# Power.net
KiCad netlist of a schematic drawn in Altium Designer
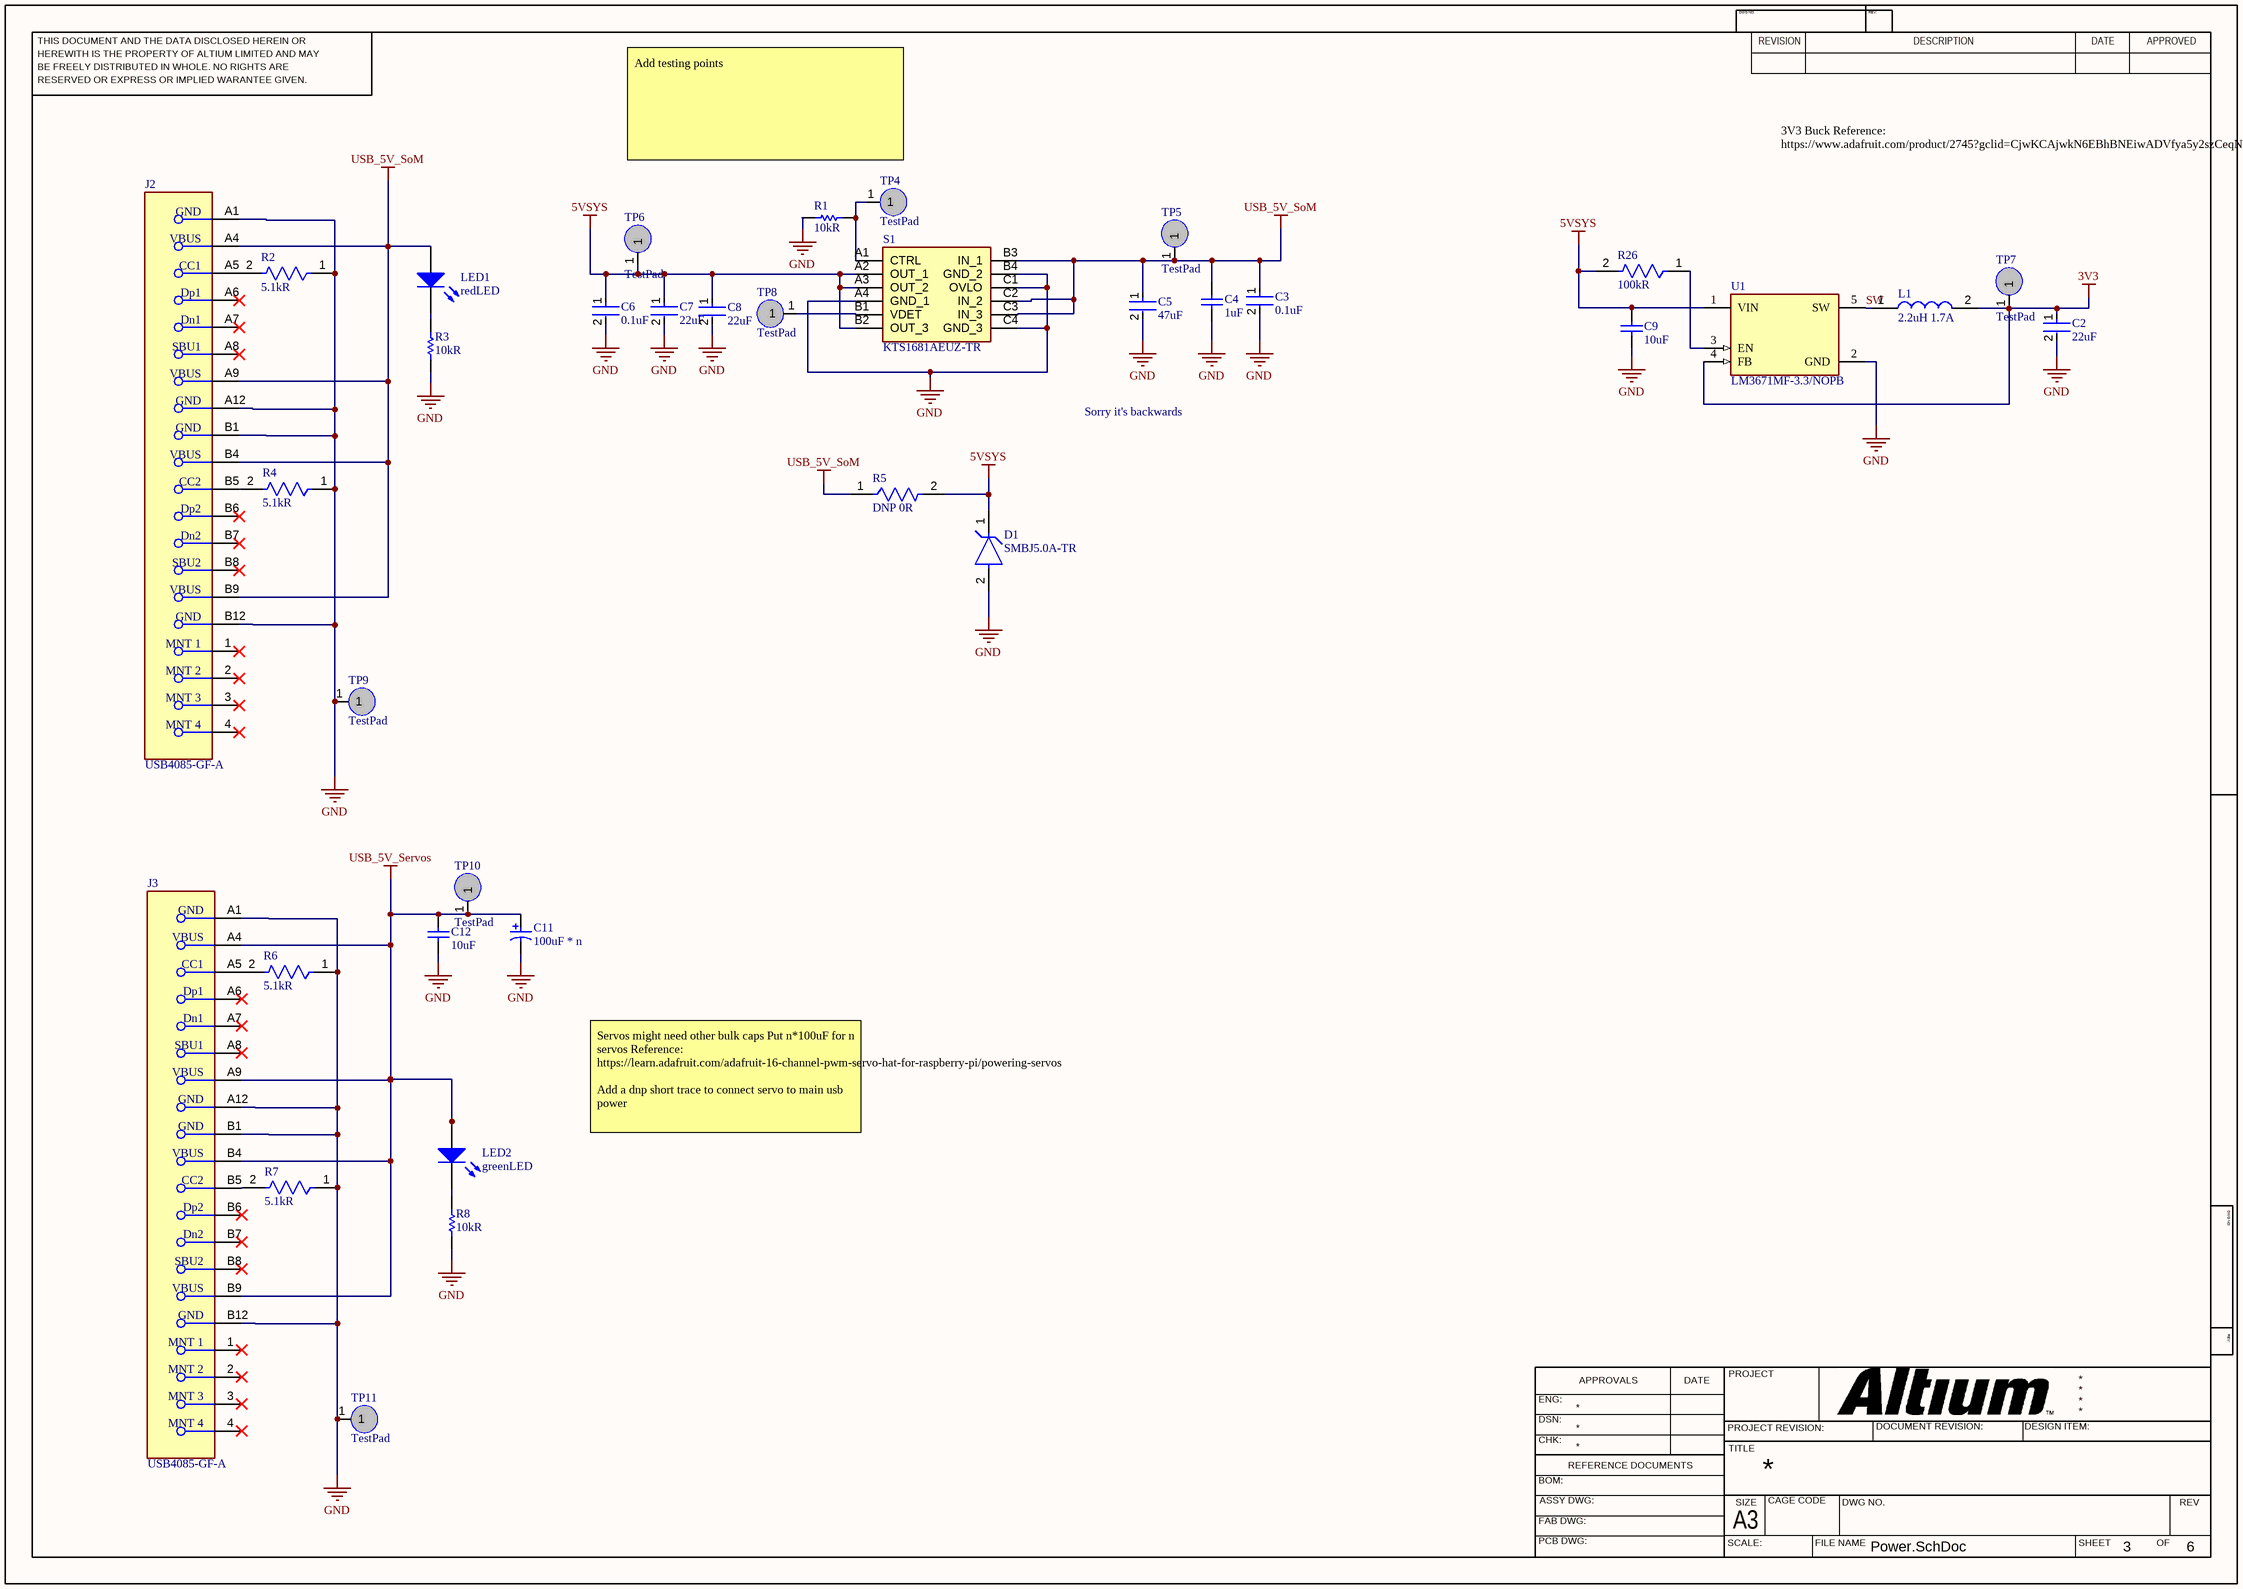
[diagram p0: Power.SchDoc]

(export (version "E")
  (design (tool "Eeschema 10.0.6"))
  (components
    (comp (ref "C2")
      (value "22uF")
      (footprint "FP-GRM21B-0_15-MFG")
      (fields (field (name "VOLTAGE") "6.3V") (field (name "TOLERANCE") "20%"))
      (libsource (lib "Altium Content Vault") (part "b4654b650e69147ec39a6b967a45e02"))
    )
    (comp (ref "C3")
      (value "0.1uF")
      (footprint "FP-C0603-CJ-MFG")
      (description "C0603X104K5RACTU CAP CER 0.1UF 50V X7R 0603")
      (fields (field (name "MANUFACTURER PART NUMBER") "C0603X104K5RACTU") (field (name "VOLTAGE") "50V"))
      (libsource (lib "Altium Content Vault") (part "11868f565c42a9108669ba33697ecf6"))
    )
    (comp (ref "C4")
      (value "1uF")
      (footprint "CAPC2013X145X50LL20T25")
      (description "C0805C105K4PACTU")
      (fields (field (name "MANUFACTURER") "Kemet"))
      (libsource (lib "Altium Content Vault") (part "CAP"))
    )
    (comp (ref "C5")
      (value "47uF")
      (footprint "FP-GRM31C-0_2-e0_3_0_8-IPC_C")
      (fields (field (name "TOLERANCE") "20%") (field (name "VOLTAGE") "6.3V"))
      (libsource (lib "Altium Content Vault") (part "02cd4be3c70576c341d710602a673aa"))
    )
    (comp (ref "C6")
      (value "0.1uF")
      (footprint "FP-C0603-CJ-MFG")
      (description "C0603X104K5RACTU CAP CER 0.1UF 50V X7R 0603")
      (fields (field (name "MANUFACTURER PART NUMBER") "C0603X104K5RACTU") (field (name "VOLTAGE") "50V"))
      (libsource (lib "Altium Content Vault") (part "11868f565c42a9108669ba33697ecf6"))
    )
    (comp (ref "C7")
      (value "22uF")
      (footprint "FP-GRM21B-0_15-MFG")
      (fields (field (name "VOLTAGE") "6.3V") (field (name "TOLERANCE") "20%"))
      (libsource (lib "Altium Content Vault") (part "b4654b650e69147ec39a6b967a45e02"))
    )
    (comp (ref "C8")
      (value "22uF")
      (footprint "FP-GRM21B-0_15-MFG")
      (fields (field (name "VOLTAGE") "6.3V") (field (name "TOLERANCE") "20%"))
      (libsource (lib "Altium Content Vault") (part "b4654b650e69147ec39a6b967a45e02"))
    )
    (comp (ref "C9")
      (value "10uF")
      (footprint "CAPC2013X145X20ML20")
      (fields
        (field (name "MANUFACTURER") "TDK")
        (field (name "TOLERANCE") "±10%")
        (field (name "PCN PART NUMBER") "MLCCPartNumberChange30/Nov/2012")
      )
      (libsource (lib "Altium Content Vault") (part "CAP-NP-2"))
    )
    (comp (ref "C11")
      (value "100uF * n")
      (footprint "CAPPR65-500-2000X1250X2200")
      (fields (field (name "MANUFACTURER") "Panasonic"))
      (libsource (lib "Altium Content Vault") (part "CAP-P-2"))
    )
    (comp (ref "C12")
      (value "10uF")
      (footprint "CAPC2013X145X20ML20")
      (fields
        (field (name "MANUFACTURER") "TDK")
        (field (name "TOLERANCE") "±10%")
        (field (name "PCN PART NUMBER") "MLCCPartNumberChange30/Nov/2012")
      )
      (libsource (lib "Altium Content Vault") (part "CAP-NP-2"))
    )
    (comp (ref "D1")
      (value "SMBJ5.0A-TR")
      (footprint "FP-SMB-MFG")
      (description "TVS DIODE 5V 13.4V SMB")
      (fields
        (field (name "MANUFACTURER") "STMicroelectronics")
        (field (name "OCTOPART") "https://octopart.com/smbj5.0a-tr-stmicroelectronics-347079")
      )
      (libsource (lib "Altium Content Vault") (part "7ddec9f632b8482e96f7745d0fbdf39"))
    )
    (comp (ref "J2")
      (value "USB4085-GF-A")
      (footprint "FP-USB4085-GF-A-MFG")
      (description "CONN RCPT USB2.0 TYPEC 16POS")
      (fields
        (field (name "MANUFACTURER") "Global Connector Technology")
        (field (name "OCTOPART") "https://octopart.com/usb4085-gf-a-global+connector+technology-94773699")
      )
      (libsource (lib "Altium Content Vault") (part "f6997dba88850a18107ac0013977506"))
    )
    (comp (ref "J3")
      (value "USB4085-GF-A")
      (footprint "FP-USB4085-GF-A-MFG")
      (description "CONN RCPT USB2.0 TYPEC 16POS")
      (fields
        (field (name "MANUFACTURER") "Global Connector Technology")
        (field (name "OCTOPART") "https://octopart.com/usb4085-gf-a-global+connector+technology-94773699")
      )
      (libsource (lib "Altium Content Vault") (part "f6997dba88850a18107ac0013977506"))
    )
    (comp (ref "L1")
      (value "2.2uH 1.7A")
      (footprint "LayoutFootprintsGoogle:NRH2412T2R2MNGH")
      (description "Inductor NRH2412T2R2MNGH")
      (fields
        (field (name "MANUFACTURER_PART_NUMBER") "NRH2412T2R2MNGH")
        (field (name "MOUSER PART NUMBER") "963-NRH2412T2R2MNGH")
      )
      (libsource (lib "*") (part "NRH2412T2R2MNGH"))
    )
    (comp (ref "LED1")
      (value "redLED")
      (footprint "0805_A")
      (description "SMD mono-color Chip LED, WL-SMCW, Super Red")
      (fields (field (name "MANUFACTURER") "Wuerth Elektronik") (field (name "PARTNUMBER") "150080SS75000"))
      (libsource (lib "Altium Content Vault") (part "WE-LED_K1A2-2"))
    )
    (comp (ref "LED2")
      (value "greenLED")
      (footprint "0805_A")
      (description "SMD mono-color Chip LED, WL-SMCW, Green")
      (fields (field (name "PARTNUMBER") "150080GS75000") (field (name "MANUFACTURER") "Wuerth Elektronik"))
      (libsource (lib "Altium Content Vault") (part "WE-LED_K1A2-2"))
    )
    (comp (ref "R1")
      (value "10kR")
      (footprint "RESC2013X60X35NL10T20")
      (fields (field (name "MANUFACTURER") "Yageo"))
      (libsource (lib "Altium Content Vault") (part "RES-2"))
    )
    (comp (ref "R2")
      (value "5.1kR")
      (footprint "FP-CRCW0805-e3-MFG")
      (description "RES Thick Film, 5.1kΩ, 1%, 0.125W, 100ppm/°C, 0805 CRCW08055K10FKEA")
      (fields (field (name "TOLERANCE") "1%"))
      (libsource (lib "Altium Content Vault") (part "1029c3af85768c4190bb7ad29bc67b5"))
    )
    (comp (ref "R3")
      (value "10kR")
      (footprint "RESC2013X60X35ML10T20")
      (fields (field (name "TOLERANCE") "1%") (field (name "MANUFACTURER") "Yageo"))
      (libsource (lib "Altium Content Vault") (part "RES-2"))
    )
    (comp (ref "R4")
      (value "5.1kR")
      (footprint "FP-CRCW0805-e3-MFG")
      (description "RES Thick Film, 5.1kΩ, 1%, 0.125W, 100ppm/°C, 0805 CRCW08055K10FKEA")
      (fields (field (name "TOLERANCE") "1%"))
      (libsource (lib "Altium Content Vault") (part "1029c3af85768c4190bb7ad29bc67b5"))
    )
    (comp (ref "R5")
      (value "DNP 0R")
      (footprint "FP-RC1206-MFG")
      (description "RC1206JR-070RL RES SMD 0 OHM JUMPER 1/4W 1206")
      (fields
        (field (name "MANUFACTURER PART NUMBER") "RC1206JR-070RL")
        (field (name "MANUFACTURER") "YAGEO")
      )
      (libsource (lib "Altium Content Vault") (part "1029c3af85768c4190bb7ad29bc67b5"))
    )
    (comp (ref "R6")
      (value "5.1kR")
      (footprint "FP-CRCW0805-e3-MFG")
      (description "RES Thick Film, 5.1kΩ, 1%, 0.125W, 100ppm/°C, 0805 CRCW08055K10FKEA")
      (fields (field (name "TOLERANCE") "1%"))
      (libsource (lib "Altium Content Vault") (part "1029c3af85768c4190bb7ad29bc67b5"))
    )
    (comp (ref "R7")
      (value "5.1kR")
      (footprint "FP-CRCW0805-e3-MFG")
      (description "RES Thick Film, 5.1kΩ, 1%, 0.125W, 100ppm/°C, 0805 CRCW08055K10FKEA")
      (fields (field (name "TOLERANCE") "1%"))
      (libsource (lib "Altium Content Vault") (part "1029c3af85768c4190bb7ad29bc67b5"))
    )
    (comp (ref "R8")
      (value "10kR")
      (footprint "RESC2013X60X35ML10T20")
      (fields (field (name "TOLERANCE") "1%") (field (name "MANUFACTURER") "Yageo"))
      (libsource (lib "Altium Content Vault") (part "RES-2"))
    )
    (comp (ref "R26")
      (value "100kR")
      (footprint "FP-RC0603-0_55-MFG")
      (description "RC0603FR-07100KL RES SMD 100K OHM 1% 1/10W 0603")
      (fields (field (name "TOLERANCE") "1%"))
      (libsource (lib "Altium Content Vault") (part "1029c3af85768c4190bb7ad29bc67b5"))
    )
    (comp (ref "S1")
      (value "KTS1681AEUZ-TR")
      (footprint "LayoutFootprintsGoogle:KTS1681AEUZTR")
      (description "Switch")
      (libsource (lib "*") (part "KTS1681AEUZ-TR"))
    )
    (comp (ref "TP4")
      (value "TestPad")
      (footprint "TestPad50mil")
      (libsource (lib "SchemSymbolsGoogle") (part "TestPad"))
    )
    (comp (ref "TP5")
      (value "TestPad")
      (footprint "TestPad50mil")
      (libsource (lib "SchemSymbolsGoogle") (part "TestPad"))
    )
    (comp (ref "TP6")
      (value "TestPad")
      (footprint "TestPad50mil")
      (libsource (lib "SchemSymbolsGoogle") (part "TestPad"))
    )
    (comp (ref "TP7")
      (value "TestPad")
      (footprint "TestPad50mil")
      (libsource (lib "SchemSymbolsGoogle") (part "TestPad"))
    )
    (comp (ref "TP8")
      (value "TestPad")
      (footprint "TestPad50mil")
      (libsource (lib "SchemSymbolsGoogle") (part "TestPad"))
    )
    (comp (ref "TP9")
      (value "TestPad")
      (footprint "TestPad50mil")
      (libsource (lib "SchemSymbolsGoogle") (part "TestPad"))
    )
    (comp (ref "TP10")
      (value "TestPad")
      (footprint "TestPad50mil")
      (libsource (lib "SchemSymbolsGoogle") (part "TestPad"))
    )
    (comp (ref "TP11")
      (value "TestPad")
      (footprint "TestPad50mil")
      (libsource (lib "SchemSymbolsGoogle") (part "TestPad"))
    )
    (comp (ref "U1")
      (value "LM3671MF-3.3/NOPB")
      (footprint "FP-DBV0005A-IPC_C")
      (description "IC REG BUCK 3.3V 600MA SOT23-5")
      (libsource (lib "Altium Content Vault") (part "6d197bdb01e3056b44211661dc106cd"))
    )
  )
  (nets
    (net (code "1") (name "/SW") (class "Default")
      (node (ref "L1") (pin "1") (pinfunction "1_1") (pintype "passive"))
      (node (ref "U1") (pin "5") (pinfunction "SW_5") (pintype "power_in"))
    )
    (net (code "2") (name "3V3") (class "Default")
      (node (ref "C2") (pin "1") (pinfunction "1_1") (pintype "passive"))
      (node (ref "L1") (pin "2") (pinfunction "2_2") (pintype "passive"))
      (node (ref "TP7") (pin "1") (pinfunction "1_1") (pintype "passive"))
      (node (ref "U1") (pin "4") (pinfunction "FB_4") (pintype "input"))
    )
    (net (code "3") (name "5VSYS") (class "Default")
      (node (ref "C6") (pin "1") (pinfunction "1_1") (pintype "passive"))
      (node (ref "C7") (pin "1") (pinfunction "1_1") (pintype "passive"))
      (node (ref "C8") (pin "1") (pinfunction "1_1") (pintype "passive"))
      (node (ref "C9") (pin "2") (pinfunction "2_2") (pintype "passive"))
      (node (ref "D1") (pin "1") (pinfunction "K_1") (pintype "passive"))
      (node (ref "R26") (pin "2") (pinfunction "2_2") (pintype "passive"))
      (node (ref "R5") (pin "2") (pinfunction "2_2") (pintype "passive"))
      (node (ref "S1") (pin "A2") (pinfunction "OUT_1_A2") (pintype "passive"))
      (node (ref "S1") (pin "A3") (pinfunction "OUT_2_A3") (pintype "passive"))
      (node (ref "S1") (pin "B2") (pinfunction "OUT_3_B2") (pintype "passive"))
      (node (ref "TP6") (pin "1") (pinfunction "1_1") (pintype "passive"))
      (node (ref "U1") (pin "1") (pinfunction "VIN_1") (pintype "power_in"))
    )
    (net (code "4") (name "GND") (class "Default")
      (node (ref "C11") (pin "2") (pinfunction "2_2") (pintype "passive"))
      (node (ref "C12") (pin "1") (pinfunction "1_1") (pintype "passive"))
      (node (ref "C2") (pin "2") (pinfunction "2_2") (pintype "passive"))
      (node (ref "C3") (pin "2") (pinfunction "2_2") (pintype "passive"))
      (node (ref "C4") (pin "1") (pinfunction "1_1") (pintype "passive"))
      (node (ref "C5") (pin "2") (pinfunction "2_2") (pintype "passive"))
      (node (ref "C6") (pin "2") (pinfunction "2_2") (pintype "passive"))
      (node (ref "C7") (pin "2") (pinfunction "2_2") (pintype "passive"))
      (node (ref "C8") (pin "2") (pinfunction "2_2") (pintype "passive"))
      (node (ref "C9") (pin "1") (pinfunction "1_1") (pintype "passive"))
      (node (ref "D1") (pin "2") (pinfunction "A_2") (pintype "passive"))
      (node (ref "J2") (pin "A1") (pinfunction "GND_A1") (pintype "power_in"))
      (node (ref "J2") (pin "A12") (pinfunction "GND_A12") (pintype "power_in"))
      (node (ref "J2") (pin "B1") (pinfunction "GND_B1") (pintype "power_in"))
      (node (ref "J2") (pin "B12") (pinfunction "GND_B12") (pintype "power_in"))
      (node (ref "J3") (pin "A1") (pinfunction "GND_A1") (pintype "power_in"))
      (node (ref "J3") (pin "A12") (pinfunction "GND_A12") (pintype "power_in"))
      (node (ref "J3") (pin "B1") (pinfunction "GND_B1") (pintype "power_in"))
      (node (ref "J3") (pin "B12") (pinfunction "GND_B12") (pintype "power_in"))
      (node (ref "R1") (pin "2") (pinfunction "2_2") (pintype "passive"))
      (node (ref "R2") (pin "1") (pinfunction "1_1") (pintype "passive"))
      (node (ref "R3") (pin "1") (pinfunction "1_1") (pintype "passive"))
      (node (ref "R4") (pin "1") (pinfunction "1_1") (pintype "passive"))
      (node (ref "R6") (pin "1") (pinfunction "1_1") (pintype "passive"))
      (node (ref "R7") (pin "1") (pinfunction "1_1") (pintype "passive"))
      (node (ref "R8") (pin "1") (pinfunction "1_1") (pintype "passive"))
      (node (ref "S1") (pin "A4") (pinfunction "GND_1_A4") (pintype "passive"))
      (node (ref "S1") (pin "B4") (pinfunction "GND_2_B4") (pintype "passive"))
      (node (ref "S1") (pin "C1") (pinfunction "OVLO_C1") (pintype "passive"))
      (node (ref "S1") (pin "C4") (pinfunction "GND_3_C4") (pintype "passive"))
      (node (ref "TP11") (pin "1") (pinfunction "1_1") (pintype "passive"))
      (node (ref "TP9") (pin "1") (pinfunction "1_1") (pintype "passive"))
      (node (ref "U1") (pin "2") (pinfunction "GND_2") (pintype "power_in"))
    )
    (net (code "5") (name "Net-(J2-CC1)") (class "Default")
      (node (ref "J2") (pin "A5") (pinfunction "CC1_A5") (pintype "passive"))
      (node (ref "R2") (pin "2") (pinfunction "2_2") (pintype "passive"))
    )
    (net (code "6") (name "Net-(J2-CC2)") (class "Default")
      (node (ref "J2") (pin "B5") (pinfunction "CC2_B5") (pintype "passive"))
      (node (ref "R4") (pin "2") (pinfunction "2_2") (pintype "passive"))
    )
    (net (code "7") (name "Net-(J3-CC1)") (class "Default")
      (node (ref "J3") (pin "A5") (pinfunction "CC1_A5") (pintype "passive"))
      (node (ref "R6") (pin "2") (pinfunction "2_2") (pintype "passive"))
    )
    (net (code "8") (name "Net-(J3-CC2)") (class "Default")
      (node (ref "J3") (pin "B5") (pinfunction "CC2_B5") (pintype "passive"))
      (node (ref "R7") (pin "2") (pinfunction "2_2") (pintype "passive"))
    )
    (net (code "9") (name "Net-(LED1-K)") (class "Default")
      (node (ref "LED1") (pin "1") (pinfunction "K_1") (pintype "passive"))
      (node (ref "R3") (pin "2") (pinfunction "2_2") (pintype "passive"))
    )
    (net (code "10") (name "Net-(LED2-K)") (class "Default")
      (node (ref "LED2") (pin "1") (pinfunction "K_1") (pintype "passive"))
      (node (ref "R8") (pin "2") (pinfunction "2_2") (pintype "passive"))
    )
    (net (code "11") (name "Net-(S1-CTRL)") (class "Default")
      (node (ref "R1") (pin "1") (pinfunction "1_1") (pintype "passive"))
      (node (ref "S1") (pin "A1") (pinfunction "CTRL_A1") (pintype "passive"))
      (node (ref "TP4") (pin "1") (pinfunction "1_1") (pintype "passive"))
    )
    (net (code "12") (name "Net-(S1-VDET)") (class "Default")
      (node (ref "S1") (pin "B1") (pinfunction "VDET_B1") (pintype "passive"))
      (node (ref "TP8") (pin "1") (pinfunction "1_1") (pintype "passive"))
    )
    (net (code "13") (name "Net-(U1-EN)") (class "Default")
      (node (ref "R26") (pin "1") (pinfunction "1_1") (pintype "passive"))
      (node (ref "U1") (pin "3") (pinfunction "EN_3") (pintype "input"))
    )
    (net (code "14") (name "USB_5V_Servos") (class "Default")
      (node (ref "C11") (pin "1") (pinfunction "1_1") (pintype "passive"))
      (node (ref "C12") (pin "2") (pinfunction "2_2") (pintype "passive"))
      (node (ref "J3") (pin "A4") (pinfunction "VBUS_A4") (pintype "power_in"))
      (node (ref "J3") (pin "A9") (pinfunction "VBUS_A9") (pintype "power_in"))
      (node (ref "J3") (pin "B4") (pinfunction "VBUS_B4") (pintype "power_in"))
      (node (ref "J3") (pin "B9") (pinfunction "VBUS_B9") (pintype "power_in"))
      (node (ref "LED2") (pin "2") (pinfunction "A_2") (pintype "passive"))
      (node (ref "TP10") (pin "1") (pinfunction "1_1") (pintype "passive"))
    )
    (net (code "15") (name "USB_5V_SoM") (class "Default")
      (node (ref "C3") (pin "1") (pinfunction "1_1") (pintype "passive"))
      (node (ref "C4") (pin "2") (pinfunction "2_2") (pintype "passive"))
      (node (ref "C5") (pin "1") (pinfunction "1_1") (pintype "passive"))
      (node (ref "J2") (pin "A4") (pinfunction "VBUS_A4") (pintype "power_in"))
      (node (ref "J2") (pin "A9") (pinfunction "VBUS_A9") (pintype "power_in"))
      (node (ref "J2") (pin "B4") (pinfunction "VBUS_B4") (pintype "power_in"))
      (node (ref "J2") (pin "B9") (pinfunction "VBUS_B9") (pintype "power_in"))
      (node (ref "LED1") (pin "2") (pinfunction "A_2") (pintype "passive"))
      (node (ref "R5") (pin "1") (pinfunction "1_1") (pintype "passive"))
      (node (ref "S1") (pin "B3") (pinfunction "IN_1_B3") (pintype "passive"))
      (node (ref "S1") (pin "C2") (pinfunction "IN_2_C2") (pintype "passive"))
      (node (ref "S1") (pin "C3") (pinfunction "IN_3_C3") (pintype "passive"))
      (node (ref "TP5") (pin "1") (pinfunction "1_1") (pintype "passive"))
    )
    (net (code "16") (name "unconnected-(J2-Dn1-PadA7)") (class "Default")
      (node (ref "J2") (pin "A7") (pinfunction "Dn1_A7") (pintype "passive+no_connect"))
    )
    (net (code "17") (name "unconnected-(J2-Dn2-PadB7)") (class "Default")
      (node (ref "J2") (pin "B7") (pinfunction "Dn2_B7") (pintype "passive+no_connect"))
    )
    (net (code "18") (name "unconnected-(J2-Dp1-PadA6)") (class "Default")
      (node (ref "J2") (pin "A6") (pinfunction "Dp1_A6") (pintype "passive+no_connect"))
    )
    (net (code "19") (name "unconnected-(J2-Dp2-PadB6)") (class "Default")
      (node (ref "J2") (pin "B6") (pinfunction "Dp2_B6") (pintype "passive+no_connect"))
    )
    (net (code "20") (name "unconnected-(J2-MNT_1-Pad1)") (class "Default")
      (node (ref "J2") (pin "1") (pinfunction "MNT_1_1") (pintype "passive+no_connect"))
    )
    (net (code "21") (name "unconnected-(J2-MNT_2-Pad2)") (class "Default")
      (node (ref "J2") (pin "2") (pinfunction "MNT_2_2") (pintype "passive+no_connect"))
    )
    (net (code "22") (name "unconnected-(J2-MNT_3-Pad3)") (class "Default")
      (node (ref "J2") (pin "3") (pinfunction "MNT_3_3") (pintype "passive+no_connect"))
    )
    (net (code "23") (name "unconnected-(J2-MNT_4-Pad4)") (class "Default")
      (node (ref "J2") (pin "4") (pinfunction "MNT_4_4") (pintype "passive+no_connect"))
    )
    (net (code "24") (name "unconnected-(J2-SBU1-PadA8)") (class "Default")
      (node (ref "J2") (pin "A8") (pinfunction "SBU1_A8") (pintype "passive+no_connect"))
    )
    (net (code "25") (name "unconnected-(J2-SBU2-PadB8)") (class "Default")
      (node (ref "J2") (pin "B8") (pinfunction "SBU2_B8") (pintype "passive+no_connect"))
    )
    (net (code "26") (name "unconnected-(J3-Dn1-PadA7)") (class "Default")
      (node (ref "J3") (pin "A7") (pinfunction "Dn1_A7") (pintype "passive+no_connect"))
    )
    (net (code "27") (name "unconnected-(J3-Dn2-PadB7)") (class "Default")
      (node (ref "J3") (pin "B7") (pinfunction "Dn2_B7") (pintype "passive+no_connect"))
    )
    (net (code "28") (name "unconnected-(J3-Dp1-PadA6)") (class "Default")
      (node (ref "J3") (pin "A6") (pinfunction "Dp1_A6") (pintype "passive+no_connect"))
    )
    (net (code "29") (name "unconnected-(J3-Dp2-PadB6)") (class "Default")
      (node (ref "J3") (pin "B6") (pinfunction "Dp2_B6") (pintype "passive+no_connect"))
    )
    (net (code "30") (name "unconnected-(J3-MNT_1-Pad1)") (class "Default")
      (node (ref "J3") (pin "1") (pinfunction "MNT_1_1") (pintype "passive+no_connect"))
    )
    (net (code "31") (name "unconnected-(J3-MNT_2-Pad2)") (class "Default")
      (node (ref "J3") (pin "2") (pinfunction "MNT_2_2") (pintype "passive+no_connect"))
    )
    (net (code "32") (name "unconnected-(J3-MNT_3-Pad3)") (class "Default")
      (node (ref "J3") (pin "3") (pinfunction "MNT_3_3") (pintype "passive+no_connect"))
    )
    (net (code "33") (name "unconnected-(J3-MNT_4-Pad4)") (class "Default")
      (node (ref "J3") (pin "4") (pinfunction "MNT_4_4") (pintype "passive+no_connect"))
    )
    (net (code "34") (name "unconnected-(J3-SBU1-PadA8)") (class "Default")
      (node (ref "J3") (pin "A8") (pinfunction "SBU1_A8") (pintype "passive+no_connect"))
    )
    (net (code "35") (name "unconnected-(J3-SBU2-PadB8)") (class "Default")
      (node (ref "J3") (pin "B8") (pinfunction "SBU2_B8") (pintype "passive+no_connect"))
    )
  )
)
